# Orthogon_-_driver_pixels.net
KiCad netlist of a schematic drawn in EAGLE
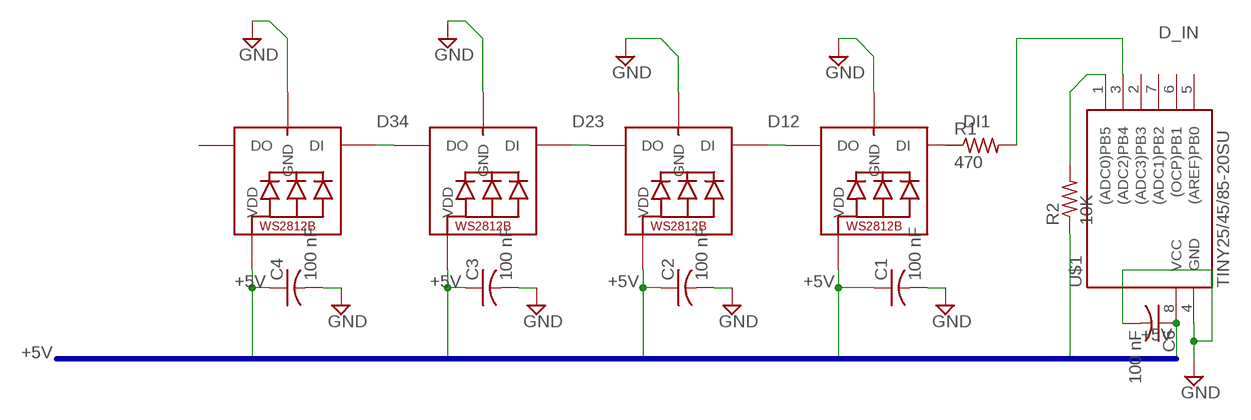
[diagram p0: schematic, sheet 1]

(export (version "E")
  (design (tool "Eeschema 10.0.6"))
  (components
    (comp (ref "C1")
      (value "100 nF")
      (footprint "eagle-import:C0402")
      (libsource (lib "eagle-import") (part "C-USC0402"))
    )
    (comp (ref "C2")
      (value "100 nF")
      (footprint "eagle-import:C0402")
      (libsource (lib "eagle-import") (part "C-USC0402"))
    )
    (comp (ref "C3")
      (value "100 nF")
      (footprint "eagle-import:C0402")
      (libsource (lib "eagle-import") (part "C-USC0402"))
    )
    (comp (ref "C4")
      (value "100 nF")
      (footprint "eagle-import:C0402")
      (libsource (lib "eagle-import") (part "C-USC0402"))
    )
    (comp (ref "C6")
      (value "100 nF")
      (footprint "eagle-import:C0402")
      (libsource (lib "eagle-import") (part "C-USC0402"))
    )
    (comp (ref "LED2")
      (value "WS2812B3535")
      (footprint "eagle-import:LED3535")
      (libsource (lib "eagle-import") (part "WS2812B3535"))
    )
    (comp (ref "LED3")
      (value "WS2812B3535")
      (footprint "eagle-import:LED3535")
      (libsource (lib "eagle-import") (part "WS2812B3535"))
    )
    (comp (ref "LED4")
      (value "WS2812B3535")
      (footprint "eagle-import:LED3535")
      (libsource (lib "eagle-import") (part "WS2812B3535"))
    )
    (comp (ref "LED5")
      (value "WS2812B3535")
      (footprint "eagle-import:LED3535")
      (libsource (lib "eagle-import") (part "WS2812B3535"))
    )
    (comp (ref "R1")
      (value "470")
      (footprint "eagle-import:R0402")
      (libsource (lib "eagle-import") (part "R-US_R0402"))
    )
    (comp (ref "R2")
      (value "10K")
      (footprint "eagle-import:R0402")
      (libsource (lib "eagle-import") (part "R-US_R0402"))
    )
    (comp (ref "U$1")
      (value "TINY25/45/85-20SU")
      (footprint "eagle-import:SOIC8")
      (libsource (lib "eagle-import") (part "TINY25/45/85-20SU"))
    )
  )
  (nets
    (net (code "1") (name "/+5V") (class "Default")
      (node (ref "C1") (pin "1") (pinfunction "1_1") (pintype "passive"))
      (node (ref "C2") (pin "1") (pinfunction "1_1") (pintype "passive"))
      (node (ref "C3") (pin "1") (pinfunction "1_1") (pintype "passive"))
      (node (ref "C4") (pin "1") (pinfunction "1_1") (pintype "passive"))
      (node (ref "C6") (pin "1") (pinfunction "1_1") (pintype "passive"))
      (node (ref "LED2") (pin "2") (pinfunction "VDD_2") (pintype "power_in"))
      (node (ref "LED3") (pin "2") (pinfunction "VDD_2") (pintype "power_in"))
      (node (ref "LED4") (pin "2") (pinfunction "VDD_2") (pintype "power_in"))
      (node (ref "LED5") (pin "2") (pinfunction "VDD_2") (pintype "power_in"))
      (node (ref "R2") (pin "1") (pinfunction "1_1") (pintype "passive"))
      (node (ref "R2") (pin "2") (pinfunction "2_2") (pintype "passive"))
      (node (ref "U$1") (pin "1") (pinfunction "(ADC0)PB5_1") (pintype "bidirectional"))
      (node (ref "U$1") (pin "8") (pinfunction "VCC_8") (pintype "power_in"))
    )
    (net (code "2") (name "/D12") (class "Default")
      (node (ref "LED4") (pin "1") (pinfunction "DI_1") (pintype "input"))
      (node (ref "LED5") (pin "3") (pinfunction "DO_3") (pintype "output"))
    )
    (net (code "3") (name "/D23") (class "Default")
      (node (ref "LED3") (pin "1") (pinfunction "DI_1") (pintype "input"))
      (node (ref "LED4") (pin "3") (pinfunction "DO_3") (pintype "output"))
    )
    (net (code "4") (name "/D34") (class "Default")
      (node (ref "LED2") (pin "1") (pinfunction "DI_1") (pintype "input"))
      (node (ref "LED3") (pin "3") (pinfunction "DO_3") (pintype "output"))
    )
    (net (code "5") (name "/DI1") (class "Default")
      (node (ref "LED5") (pin "1") (pinfunction "DI_1") (pintype "input"))
      (node (ref "R1") (pin "1") (pinfunction "1_1") (pintype "passive"))
    )
    (net (code "6") (name "/D_IN") (class "Default")
      (node (ref "R1") (pin "2") (pinfunction "2_2") (pintype "passive"))
      (node (ref "U$1") (pin "3") (pinfunction "(ADC2)PB4_3") (pintype "bidirectional"))
    )
    (net (code "8") (name "GND") (class "Default")
      (node (ref "C1") (pin "2") (pinfunction "2_2") (pintype "passive"))
      (node (ref "C2") (pin "2") (pinfunction "2_2") (pintype "passive"))
      (node (ref "C3") (pin "2") (pinfunction "2_2") (pintype "passive"))
      (node (ref "C4") (pin "2") (pinfunction "2_2") (pintype "passive"))
      (node (ref "C6") (pin "2") (pinfunction "2_2") (pintype "passive"))
      (node (ref "LED2") (pin "4") (pinfunction "GND_4") (pintype "power_in"))
      (node (ref "LED3") (pin "4") (pinfunction "GND_4") (pintype "power_in"))
      (node (ref "LED4") (pin "4") (pinfunction "GND_4") (pintype "power_in"))
      (node (ref "LED5") (pin "4") (pinfunction "GND_4") (pintype "power_in"))
      (node (ref "U$1") (pin "4") (pinfunction "GND_4") (pintype "power_in"))
    )
    (net (code "9") (name "unconnected-(LED2-DO-Pad3)") (class "Default")
      (node (ref "LED2") (pin "3") (pinfunction "DO_3") (pintype "output"))
    )
    (net (code "10") (name "unconnected-(U$1-(ADC1)PB2-Pad7)") (class "Default")
      (node (ref "U$1") (pin "7") (pinfunction "(ADC1)PB2_7") (pintype "bidirectional"))
    )
    (net (code "11") (name "unconnected-(U$1-(ADC3)PB3-Pad2)") (class "Default")
      (node (ref "U$1") (pin "2") (pinfunction "(ADC3)PB3_2") (pintype "bidirectional"))
    )
    (net (code "12") (name "unconnected-(U$1-(AREF)PB0-Pad5)") (class "Default")
      (node (ref "U$1") (pin "5") (pinfunction "(AREF)PB0_5") (pintype "bidirectional"))
    )
    (net (code "13") (name "unconnected-(U$1-(OCP)PB1-Pad6)") (class "Default")
      (node (ref "U$1") (pin "6") (pinfunction "(OCP)PB1_6") (pintype "bidirectional"))
    )
  )
)
